# tiny45-button-2-leds-FTDI.net
KiCad netlist of a schematic drawn in EAGLE
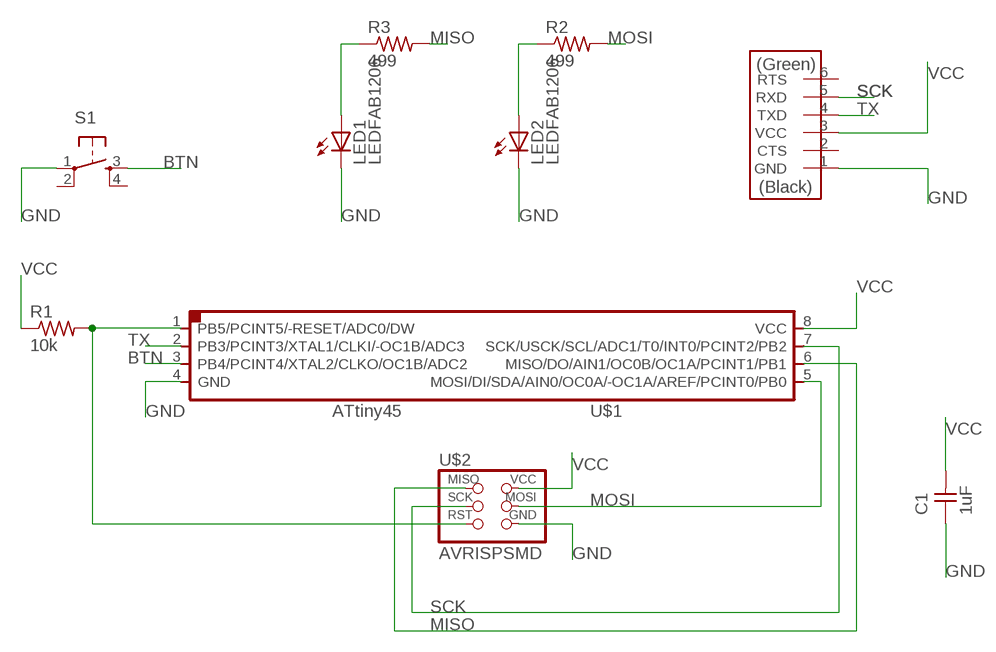
[diagram p0: schematic, sheet 1]

(export (version "E")
  (design (tool "Eeschema 10.0.6"))
  (components
    (comp (ref "C1")
      (value "1uF")
      (footprint "eagle-import:C1206FAB")
      (libsource (lib "eagle-import") (part "CAP-UNPOLARIZEDFAB"))
    )
    (comp (ref "LED1")
      (value "LEDFAB1206")
      (footprint "eagle-import:LED1206FAB")
      (libsource (lib "eagle-import") (part "LEDFAB1206"))
    )
    (comp (ref "LED2")
      (value "LEDFAB1206")
      (footprint "eagle-import:LED1206FAB")
      (libsource (lib "eagle-import") (part "LEDFAB1206"))
    )
    (comp (ref "R1")
      (value "10k")
      (footprint "eagle-import:R1206FAB")
      (libsource (lib "eagle-import") (part "RES-US1206FAB"))
    )
    (comp (ref "R2")
      (value "499")
      (footprint "eagle-import:R1206FAB")
      (libsource (lib "eagle-import") (part "RES-US1206FAB"))
    )
    (comp (ref "R3")
      (value "499")
      (footprint "eagle-import:R1206FAB")
      (libsource (lib "eagle-import") (part "RES-US1206FAB"))
    )
    (comp (ref "S1")
      (value "6MM_SWITCH6MM_SWITCH")
      (footprint "eagle-import:6MM_SWITCH")
      (libsource (lib "eagle-import") (part "6MM_SWITCH6MM_SWITCH"))
    )
    (comp (ref "U$1")
      (value "ATTINY45SI")
      (footprint "eagle-import:SOIC8")
      (libsource (lib "eagle-import") (part "ATTINY45SI"))
    )
    (comp (ref "U$2")
      (value "AVRISPSMD")
      (footprint "eagle-import:2X03SMD")
      (libsource (lib "eagle-import") (part "AVRISPSMD"))
    )
    (comp (ref "U$3")
      (value "FTDI-SMD-HEADER")
      (footprint "eagle-import:1X06SMD")
      (libsource (lib "eagle-import") (part "FTDI-SMD-HEADER"))
    )
  )
  (nets
    (net (code "1") (name "/BTN") (class "Default")
      (node (ref "S1") (pin "3") (pinfunction "S_3") (pintype "passive"))
      (node (ref "U$1") (pin "3") (pinfunction "PB4/PCINT4/XTAL2/CLKO/OC1B/ADC2_3") (pintype "bidirectional"))
    )
    (net (code "2") (name "/GND") (class "Default")
      (node (ref "C1") (pin "1") (pinfunction "1_1") (pintype "passive"))
      (node (ref "LED1") (pin "2") (pinfunction "C_2") (pintype "passive"))
      (node (ref "LED2") (pin "2") (pinfunction "C_2") (pintype "passive"))
      (node (ref "S1") (pin "1") (pinfunction "P_1") (pintype "passive"))
      (node (ref "U$1") (pin "4") (pinfunction "GND_4") (pintype "bidirectional"))
      (node (ref "U$2") (pin "6") (pinfunction "GND_6") (pintype "passive"))
      (node (ref "U$3") (pin "1") (pinfunction "GND_1") (pintype "bidirectional"))
    )
    (net (code "3") (name "/MISO") (class "Default")
      (node (ref "R3") (pin "2") (pinfunction "2_2") (pintype "passive"))
      (node (ref "U$1") (pin "6") (pinfunction "MISO/DO/AIN1/OC0B/OC1A/PCINT1/PB1_6") (pintype "bidirectional"))
      (node (ref "U$2") (pin "1") (pinfunction "MISO_1") (pintype "passive"))
    )
    (net (code "4") (name "/MOSI") (class "Default")
      (node (ref "R2") (pin "2") (pinfunction "2_2") (pintype "passive"))
      (node (ref "U$1") (pin "5") (pinfunction "MOSI/DI/SDA/AIN0/OC0A/-OC1A/AREF/PCINT0/PB0_5") (pintype "bidirectional"))
      (node (ref "U$2") (pin "4") (pinfunction "MOSI_4") (pintype "passive"))
    )
    (net (code "5") (name "/SCK") (class "Default")
      (node (ref "U$1") (pin "7") (pinfunction "SCK/USCK/SCL/ADC1/T0/INT0/PCINT2/PB2_7") (pintype "bidirectional"))
      (node (ref "U$2") (pin "3") (pinfunction "SCK_3") (pintype "passive"))
      (node (ref "U$3") (pin "5") (pinfunction "RXD_5") (pintype "bidirectional"))
    )
    (net (code "6") (name "/TX") (class "Default")
      (node (ref "U$1") (pin "2") (pinfunction "PB3/PCINT3/XTAL1/CLKI/-OC1B/ADC3_2") (pintype "bidirectional"))
      (node (ref "U$3") (pin "4") (pinfunction "TXD_4") (pintype "bidirectional"))
    )
    (net (code "7") (name "/VCC") (class "Default")
      (node (ref "C1") (pin "2") (pinfunction "2_2") (pintype "passive"))
      (node (ref "R1") (pin "1") (pinfunction "1_1") (pintype "passive"))
      (node (ref "U$1") (pin "8") (pinfunction "VCC_8") (pintype "bidirectional"))
      (node (ref "U$2") (pin "2") (pinfunction "VCC_2") (pintype "passive"))
      (node (ref "U$3") (pin "3") (pinfunction "VCC_3") (pintype "bidirectional"))
    )
    (net (code "8") (name "Net-(LED1-A)") (class "Default")
      (node (ref "LED1") (pin "1") (pinfunction "A_1") (pintype "passive"))
      (node (ref "R3") (pin "1") (pinfunction "1_1") (pintype "passive"))
    )
    (net (code "9") (name "Net-(LED2-A)") (class "Default")
      (node (ref "LED2") (pin "1") (pinfunction "A_1") (pintype "passive"))
      (node (ref "R2") (pin "1") (pinfunction "1_1") (pintype "passive"))
    )
    (net (code "10") (name "Net-(U$1-PB5{slash}PCINT5{slash}-RESET{slash}ADC0{slash}DW)") (class "Default")
      (node (ref "R1") (pin "2") (pinfunction "2_2") (pintype "passive"))
      (node (ref "U$1") (pin "1") (pinfunction "PB5/PCINT5/-RESET/ADC0/DW_1") (pintype "bidirectional"))
      (node (ref "U$2") (pin "5") (pinfunction "RST_5") (pintype "passive"))
    )
    (net (code "11") (name "unconnected-(S1-P1-Pad2)") (class "Default")
      (node (ref "S1") (pin "2") (pinfunction "P1_2") (pintype "passive"))
    )
    (net (code "12") (name "unconnected-(S1-S1-Pad4)") (class "Default")
      (node (ref "S1") (pin "4") (pinfunction "S1_4") (pintype "passive"))
    )
    (net (code "13") (name "unconnected-(U$3-CTS-Pad2)") (class "Default")
      (node (ref "U$3") (pin "2") (pinfunction "CTS_2") (pintype "bidirectional"))
    )
    (net (code "14") (name "unconnected-(U$3-RTS-Pad6)") (class "Default")
      (node (ref "U$3") (pin "6") (pinfunction "RTS_6") (pintype "bidirectional"))
    )
  )
)
